# power.net
KiCad netlist of a schematic drawn in Altium Designer
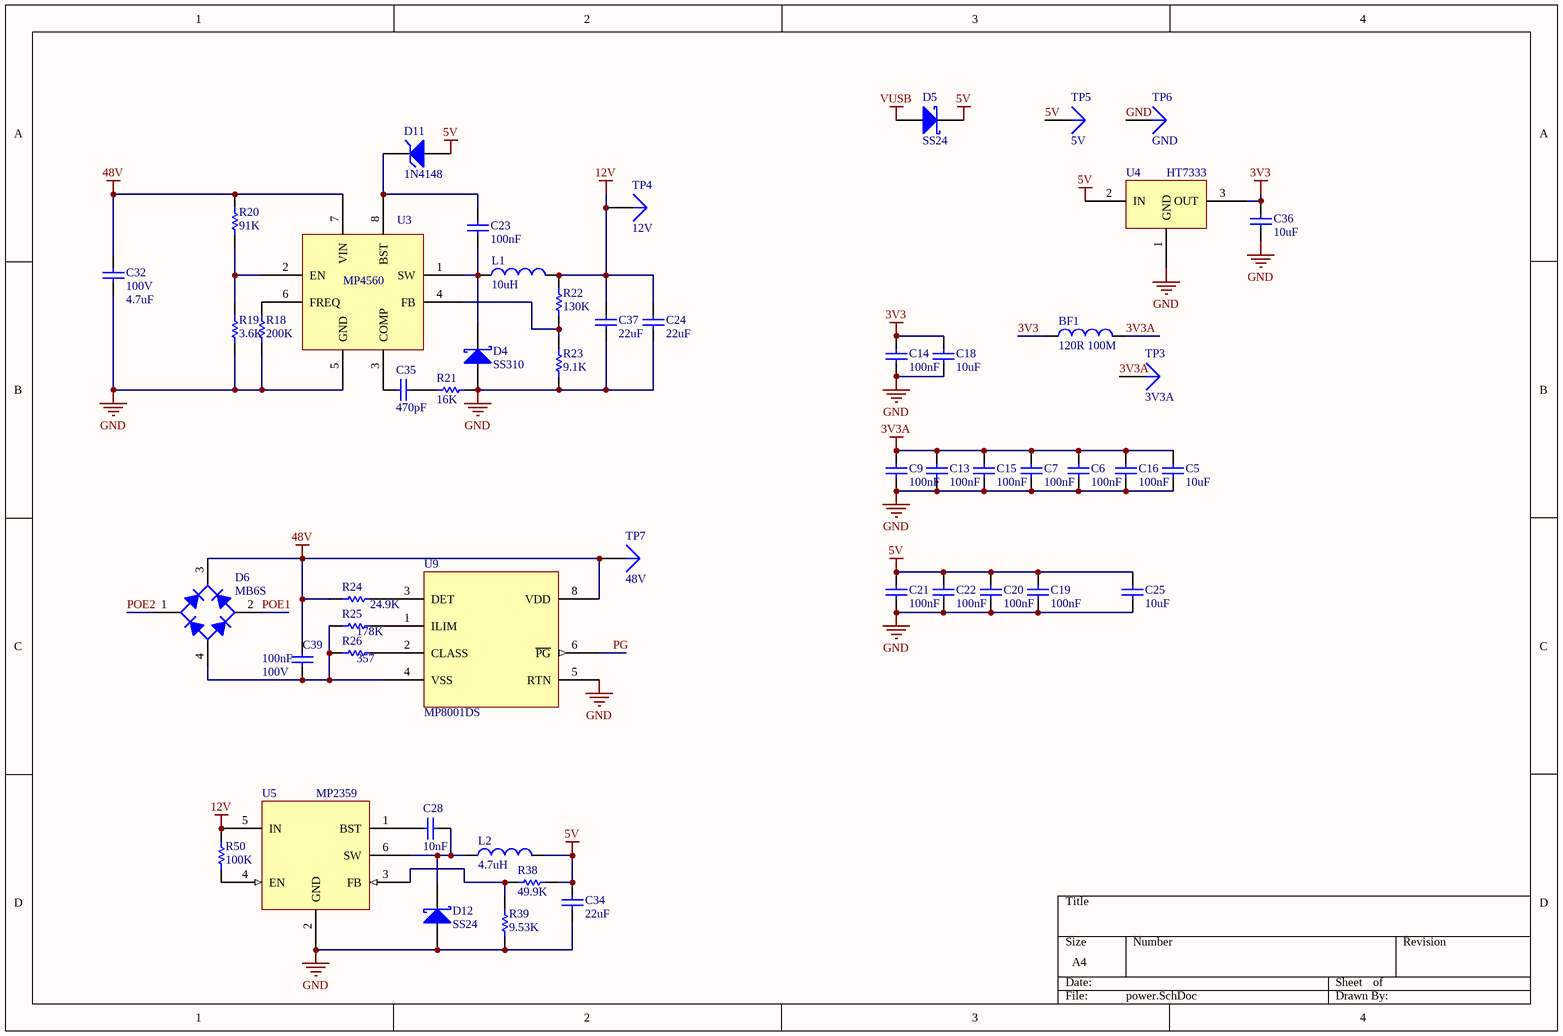
[diagram p0: power.SchDoc]

(export (version "E")
  (design (tool "Eeschema 10.0.6"))
  (components
    (comp (ref "BF1")
      (value "120R 100M")
      (footprint "L-1608[0603]")
      (fields (field (name "Comment") "GZ1608D121TF") (field (name "PUBLISHER") "Altium Limited"))
      (libsource (lib "Miscellaneous Devices") (part "Inductor"))
    )
    (comp (ref "C5")
      (value "10uF")
      (footprint "C-1608[0603]")
      (description "Capacitor (Semiconductor SIM Model)")
      (fields (field (name "Comment") "Cap Semi") (field (name "PUBLISHER") "Altium Limited"))
      (libsource (lib "Miscellaneous Devices") (part "Cap Semi"))
    )
    (comp (ref "C6")
      (value "100nF")
      (footprint "C-1608[0603]")
      (description "Capacitor (Semiconductor SIM Model)")
      (fields (field (name "Comment") "Cap Semi") (field (name "PUBLISHER") "Altium Limited"))
      (libsource (lib "Miscellaneous Devices") (part "Cap Semi"))
    )
    (comp (ref "C7")
      (value "100nF")
      (footprint "C-1608[0603]")
      (description "Capacitor (Semiconductor SIM Model)")
      (fields (field (name "Comment") "Cap Semi") (field (name "PUBLISHER") "Altium Limited"))
      (libsource (lib "Miscellaneous Devices") (part "Cap Semi"))
    )
    (comp (ref "C9")
      (value "100nF")
      (footprint "C-1608[0603]")
      (description "Capacitor (Semiconductor SIM Model)")
      (fields (field (name "Comment") "Cap Semi") (field (name "PUBLISHER") "Altium Limited"))
      (libsource (lib "Miscellaneous Devices") (part "Cap Semi"))
    )
    (comp (ref "C13")
      (value "100nF")
      (footprint "C-1608[0603]")
      (description "Capacitor (Semiconductor SIM Model)")
      (fields (field (name "Comment") "Cap Semi") (field (name "PUBLISHER") "Altium Limited"))
      (libsource (lib "Miscellaneous Devices") (part "Cap Semi"))
    )
    (comp (ref "C14")
      (value "100nF")
      (footprint "C-1608[0603]")
      (description "Capacitor (Semiconductor SIM Model)")
      (fields (field (name "Comment") "Cap Semi") (field (name "PUBLISHER") "Altium Limited"))
      (libsource (lib "Miscellaneous Devices") (part "Cap Semi"))
    )
    (comp (ref "C15")
      (value "100nF")
      (footprint "C-1608[0603]")
      (description "Capacitor (Semiconductor SIM Model)")
      (fields (field (name "Comment") "Cap Semi") (field (name "PUBLISHER") "Altium Limited"))
      (libsource (lib "Miscellaneous Devices") (part "Cap Semi"))
    )
    (comp (ref "C16")
      (value "100nF")
      (footprint "C-1608[0603]")
      (description "Capacitor (Semiconductor SIM Model)")
      (fields (field (name "Comment") "Cap Semi") (field (name "PUBLISHER") "Altium Limited"))
      (libsource (lib "Miscellaneous Devices") (part "Cap Semi"))
    )
    (comp (ref "C18")
      (value "10uF")
      (footprint "C-1608[0603]")
      (description "Capacitor (Semiconductor SIM Model)")
      (fields (field (name "Comment") "Cap Semi") (field (name "PUBLISHER") "Altium Limited"))
      (libsource (lib "Miscellaneous Devices") (part "Cap Semi"))
    )
    (comp (ref "C19")
      (value "100nF")
      (footprint "C-1608[0603]")
      (description "Capacitor (Semiconductor SIM Model)")
      (fields (field (name "Comment") "Cap Semi") (field (name "PUBLISHER") "Altium Limited"))
      (libsource (lib "Miscellaneous Devices") (part "Cap Semi"))
    )
    (comp (ref "C20")
      (value "100nF")
      (footprint "C-1608[0603]")
      (description "Capacitor (Semiconductor SIM Model)")
      (fields (field (name "Comment") "Cap Semi") (field (name "PUBLISHER") "Altium Limited"))
      (libsource (lib "Miscellaneous Devices") (part "Cap Semi"))
    )
    (comp (ref "C21")
      (value "100nF")
      (footprint "C-1608[0603]")
      (description "Capacitor (Semiconductor SIM Model)")
      (fields (field (name "Comment") "Cap Semi") (field (name "PUBLISHER") "Altium Limited"))
      (libsource (lib "Miscellaneous Devices") (part "Cap Semi"))
    )
    (comp (ref "C22")
      (value "100nF")
      (footprint "C-1608[0603]")
      (description "Capacitor (Semiconductor SIM Model)")
      (fields (field (name "Comment") "Cap Semi") (field (name "PUBLISHER") "Altium Limited"))
      (libsource (lib "Miscellaneous Devices") (part "Cap Semi"))
    )
    (comp (ref "C23")
      (value "100nF")
      (footprint "C-1608[0603]")
      (description "Capacitor (Semiconductor SIM Model)")
      (fields (field (name "Comment") "Cap Semi") (field (name "PUBLISHER") "Altium Limited"))
      (libsource (lib "Miscellaneous Devices") (part "Cap Semi"))
    )
    (comp (ref "C24")
      (value "22uF")
      (footprint "CAPC3225L")
      (description "Capacitor (Semiconductor SIM Model)")
      (fields (field (name "Comment") "Cap Semi") (field (name "PUBLISHER") "Altium Limited"))
      (libsource (lib "Miscellaneous Devices") (part "Cap Semi"))
    )
    (comp (ref "C25")
      (value "10uF")
      (footprint "C-1608[0603]")
      (description "Capacitor (Semiconductor SIM Model)")
      (fields (field (name "Comment") "Cap Semi") (field (name "PUBLISHER") "Altium Limited"))
      (libsource (lib "Miscellaneous Devices") (part "Cap Semi"))
    )
    (comp (ref "C28")
      (value "10nF")
      (footprint "C-1608[0603]")
      (description "Capacitor (Semiconductor SIM Model)")
      (fields (field (name "Comment") "Cap Semi") (field (name "PUBLISHER") "Altium Limited"))
      (libsource (lib "Miscellaneous Devices") (part "Cap Semi"))
    )
    (comp (ref "C32")
      (value "100V")
      (footprint "CAPC3216L")
      (description "Capacitor (Semiconductor SIM Model)")
      (fields (field (name "ALTIUM_VALUE") "4.7uF") (field (name "PUBLISHER") "Altium Limited"))
      (libsource (lib "Miscellaneous Devices") (part "Cap Semi"))
    )
    (comp (ref "C34")
      (value "22uF")
      (footprint "CAPC2512L")
      (description "Capacitor (Semiconductor SIM Model)")
      (fields (field (name "Comment") "Tantalum") (field (name "PUBLISHER") "Altium Limited"))
      (libsource (lib "Miscellaneous Devices") (part "Cap Semi"))
    )
    (comp (ref "C35")
      (value "470pF")
      (footprint "C-1608[0603]")
      (description "Capacitor (Semiconductor SIM Model)")
      (fields (field (name "Comment") "Cap Semi") (field (name "PUBLISHER") "Altium Limited"))
      (libsource (lib "Miscellaneous Devices") (part "Cap Semi"))
    )
    (comp (ref "C36")
      (value "10uF")
      (footprint "CAPC2512L")
      (description "Capacitor (Semiconductor SIM Model)")
      (fields (field (name "Comment") "Tantalum") (field (name "PUBLISHER") "Altium Limited"))
      (libsource (lib "Miscellaneous Devices") (part "Cap Semi"))
    )
    (comp (ref "C37")
      (value "22uF")
      (footprint "CAPC3225L")
      (description "Capacitor (Semiconductor SIM Model)")
      (fields (field (name "Comment") "Cap Semi") (field (name "PUBLISHER") "Altium Limited"))
      (libsource (lib "Miscellaneous Devices") (part "Cap Semi"))
    )
    (comp (ref "C39")
      (value "100V")
      (footprint "C-2012[0805]")
      (description "Capacitor (Semiconductor SIM Model)")
      (fields (field (name "ALTIUM_VALUE") "100nF") (field (name "PUBLISHER") "Altium Limited"))
      (libsource (lib "Miscellaneous Devices") (part "Cap Semi"))
    )
    (comp (ref "D4")
      (value "SS310")
      (footprint "DO-214AC")
      (description "Schottky Diode")
      (fields (field (name "PUBLISHER") "Altium Limited"))
      (libsource (lib "Miscellaneous Devices") (part "D Schottky"))
    )
    (comp (ref "D5")
      (value "SS24")
      (footprint "DO-214AC")
      (description "Schottky Diode")
      (fields (field (name "PUBLISHER") "Altium Limited"))
      (libsource (lib "Miscellaneous Devices") (part "D Schottky"))
    )
    (comp (ref "D6")
      (value "MB6S")
      (footprint "MB6S")
      (description "Full Wave Diode Bridge")
      (fields (field (name "PUBLISHER") "Altium Limited"))
      (libsource (lib "Miscellaneous Devices") (part "Bridge1"))
    )
    (comp (ref "D11")
      (value "1N4148")
      (footprint "LL-34")
      (description "Zener Diode")
      (fields (field (name "PUBLISHER") "Altium Limited"))
      (libsource (lib "Miscellaneous Devices") (part "D Zener"))
    )
    (comp (ref "D12")
      (value "SS24")
      (footprint "DO-214AC")
      (description "Schottky Diode")
      (fields (field (name "PUBLISHER") "Altium Limited"))
      (libsource (lib "Miscellaneous Devices") (part "D Schottky"))
    )
    (comp (ref "L1")
      (value "10uH")
      (footprint "L-5040")
      (description "Inductor")
      (fields (field (name "PUBLISHER") "Altium Limited"))
      (libsource (lib "Miscellaneous Devices") (part "Inductor"))
    )
    (comp (ref "L2")
      (value "4.7uH")
      (footprint "INDC4532N")
      (description "Inductor")
      (fields (field (name "PUBLISHER") "Altium Limited"))
      (libsource (lib "Miscellaneous Devices") (part "Inductor"))
    )
    (comp (ref "R18")
      (value "200K")
      (footprint "R-1608[0603]")
      (description "Semiconductor Resistor")
      (fields (field (name "Comment") "Res Semi") (field (name "PUBLISHER") "Altium Limited"))
      (libsource (lib "Miscellaneous Devices") (part "Res Semi"))
    )
    (comp (ref "R19")
      (value "3.6K")
      (footprint "R-1608[0603]")
      (description "Semiconductor Resistor")
      (fields (field (name "Comment") "Res Semi") (field (name "PUBLISHER") "Altium Limited"))
      (libsource (lib "Miscellaneous Devices") (part "Res Semi"))
    )
    (comp (ref "R20")
      (value "91K")
      (footprint "R-1608[0603]")
      (description "Semiconductor Resistor")
      (fields (field (name "Comment") "Res Semi") (field (name "PUBLISHER") "Altium Limited"))
      (libsource (lib "Miscellaneous Devices") (part "Res Semi"))
    )
    (comp (ref "R21")
      (value "16K")
      (footprint "R-1608[0603]")
      (description "Semiconductor Resistor")
      (fields (field (name "Comment") "Res Semi") (field (name "PUBLISHER") "Altium Limited"))
      (libsource (lib "Miscellaneous Devices") (part "Res Semi"))
    )
    (comp (ref "R22")
      (value "130K")
      (footprint "R-1608[0603]")
      (description "Semiconductor Resistor")
      (fields (field (name "Comment") "Res Semi") (field (name "PUBLISHER") "Altium Limited"))
      (libsource (lib "Miscellaneous Devices") (part "Res Semi"))
    )
    (comp (ref "R23")
      (value "9.1K")
      (footprint "R-1608[0603]")
      (description "Semiconductor Resistor")
      (fields (field (name "Comment") "Res Semi") (field (name "PUBLISHER") "Altium Limited"))
      (libsource (lib "Miscellaneous Devices") (part "Res Semi"))
    )
    (comp (ref "R24")
      (value "24.9K")
      (footprint "R-2012[0805]")
      (description "Semiconductor Resistor")
      (fields (field (name "Comment") "1/4W") (field (name "PUBLISHER") "Altium Limited"))
      (libsource (lib "Miscellaneous Devices") (part "Res Semi"))
    )
    (comp (ref "R25")
      (value "178K")
      (footprint "R-1608[0603]")
      (description "Semiconductor Resistor")
      (fields (field (name "Comment") "Res Semi") (field (name "PUBLISHER") "Altium Limited"))
      (libsource (lib "Miscellaneous Devices") (part "Res Semi"))
    )
    (comp (ref "R26")
      (value "357")
      (footprint "R-1608[0603]")
      (description "Semiconductor Resistor")
      (fields (field (name "Comment") "Res Semi") (field (name "PUBLISHER") "Altium Limited"))
      (libsource (lib "Miscellaneous Devices") (part "Res Semi"))
    )
    (comp (ref "R38")
      (value "49.9K")
      (footprint "R-1608[0603]")
      (description "Semiconductor Resistor")
      (fields (field (name "Comment") "Res Semi") (field (name "PUBLISHER") "Altium Limited"))
      (libsource (lib "Miscellaneous Devices") (part "Res Semi"))
    )
    (comp (ref "R39")
      (value "9.53K")
      (footprint "R-1608[0603]")
      (description "Semiconductor Resistor")
      (fields (field (name "Comment") "Res Semi") (field (name "PUBLISHER") "Altium Limited"))
      (libsource (lib "Miscellaneous Devices") (part "Res Semi"))
    )
    (comp (ref "R50")
      (value "100K")
      (footprint "R-1608[0603]")
      (description "Semiconductor Resistor")
      (fields (field (name "Comment") "Res Semi") (field (name "PUBLISHER") "Altium Limited"))
      (libsource (lib "Miscellaneous Devices") (part "Res Semi"))
    )
    (comp (ref "TP3")
      (value "3V3A")
      (footprint "TESTPOINT")
      (description "Plug")
      (fields (field (name "PUBLISHER") "Altium Limited"))
      (libsource (lib "Miscellaneous Connectors") (part "Plug"))
    )
    (comp (ref "TP4")
      (value "12V")
      (footprint "TESTPOINT")
      (description "Plug")
      (fields (field (name "PUBLISHER") "Altium Limited"))
      (libsource (lib "Miscellaneous Connectors") (part "Plug"))
    )
    (comp (ref "TP5")
      (value "5V")
      (footprint "TESTPOINT")
      (description "Plug")
      (fields (field (name "PUBLISHER") "Altium Limited"))
      (libsource (lib "Miscellaneous Connectors") (part "Plug"))
    )
    (comp (ref "TP6")
      (value "GND")
      (footprint "TESTPOINT")
      (description "Plug")
      (fields (field (name "PUBLISHER") "Altium Limited"))
      (libsource (lib "Miscellaneous Connectors") (part "Plug"))
    )
    (comp (ref "TP7")
      (value "48V")
      (footprint "TESTPOINT")
      (description "Plug")
      (fields (field (name "PUBLISHER") "Altium Limited"))
      (libsource (lib "Miscellaneous Connectors") (part "Plug"))
    )
    (comp (ref "U3")
      (value "MP4560")
      (footprint "MP1584")
      (description "2A, 2MHz, 55V Step-Down Converter")
      (libsource (lib "Schlib1") (part "MP4560"))
    )
    (comp (ref "U4")
      (value "HT7333")
      (footprint "SOT89")
      (description "Low Power Consumption LDO")
      (libsource (lib "Schlib1") (part "HT73XX"))
    )
    (comp (ref "U5")
      (value "MP2359")
      (footprint "SOT23-6")
      (description "1.2A, 24V, 1.4MHz  Step-Down Converter")
      (libsource (lib "Schlib1") (part "MP2359"))
    )
    (comp (ref "U9") (value "MP8001DS") (footprint "SOIC_E150_8") (libsource (lib "Schlib1") (part "MP8001")))
  )
  (nets
    (net (code "1") (name "/PG") (class "Default")
      (node (ref "U9") (pin "6") (pinfunction "~{PG}_6") (pintype "output"))
    )
    (net (code "2") (name "/POE1") (class "Default")
      (node (ref "D6") (pin "2") (pinfunction "C_2") (pintype "passive"))
    )
    (net (code "3") (name "/POE2") (class "Default")
      (node (ref "D6") (pin "1") (pinfunction "C_1") (pintype "passive"))
    )
    (net (code "4") (name "3V3") (class "Default")
      (node (ref "BF1") (pin "1") (pinfunction "1_1") (pintype "passive"))
      (node (ref "C14") (pin "2") (pinfunction "2_2") (pintype "passive"))
      (node (ref "C18") (pin "2") (pinfunction "2_2") (pintype "passive"))
      (node (ref "C36") (pin "1") (pinfunction "1_1") (pintype "passive"))
      (node (ref "U4") (pin "3") (pinfunction "OUT_3") (pintype "passive"))
    )
    (net (code "5") (name "3V3A") (class "Default")
      (node (ref "BF1") (pin "2") (pinfunction "2_2") (pintype "passive"))
      (node (ref "C13") (pin "2") (pinfunction "2_2") (pintype "passive"))
      (node (ref "C15") (pin "2") (pinfunction "2_2") (pintype "passive"))
      (node (ref "C16") (pin "2") (pinfunction "2_2") (pintype "passive"))
      (node (ref "C5") (pin "2") (pinfunction "2_2") (pintype "passive"))
      (node (ref "C6") (pin "2") (pinfunction "2_2") (pintype "passive"))
      (node (ref "C7") (pin "2") (pinfunction "2_2") (pintype "passive"))
      (node (ref "C9") (pin "2") (pinfunction "2_2") (pintype "passive"))
      (node (ref "TP3") (pin "1") (pinfunction "1_1") (pintype "passive"))
    )
    (net (code "6") (name "5V") (class "Default")
      (node (ref "C19") (pin "2") (pinfunction "2_2") (pintype "passive"))
      (node (ref "C20") (pin "2") (pinfunction "2_2") (pintype "passive"))
      (node (ref "C21") (pin "2") (pinfunction "2_2") (pintype "passive"))
      (node (ref "C22") (pin "2") (pinfunction "2_2") (pintype "passive"))
      (node (ref "C25") (pin "2") (pinfunction "2_2") (pintype "passive"))
      (node (ref "C34") (pin "1") (pinfunction "1_1") (pintype "passive"))
      (node (ref "D11") (pin "1") (pinfunction "A_1") (pintype "passive"))
      (node (ref "D5") (pin "2") (pinfunction "K_2") (pintype "passive"))
      (node (ref "L2") (pin "2") (pinfunction "2_2") (pintype "passive"))
      (node (ref "R38") (pin "1") (pinfunction "1_1") (pintype "passive"))
      (node (ref "TP5") (pin "1") (pinfunction "1_1") (pintype "passive"))
      (node (ref "U4") (pin "2") (pinfunction "IN_2") (pintype "passive"))
    )
    (net (code "7") (name "12V") (class "Default")
      (node (ref "C24") (pin "1") (pinfunction "1_1") (pintype "passive"))
      (node (ref "C37") (pin "1") (pinfunction "1_1") (pintype "passive"))
      (node (ref "L1") (pin "2") (pinfunction "2_2") (pintype "passive"))
      (node (ref "R22") (pin "2") (pinfunction "2_2") (pintype "passive"))
      (node (ref "R50") (pin "1") (pinfunction "1_1") (pintype "passive"))
      (node (ref "TP4") (pin "1") (pinfunction "1_1") (pintype "passive"))
      (node (ref "U5") (pin "5") (pinfunction "IN_5") (pintype "power_in"))
    )
    (net (code "8") (name "48V") (class "Default")
      (node (ref "C32") (pin "2") (pinfunction "2_2") (pintype "passive"))
      (node (ref "C39") (pin "2") (pinfunction "2_2") (pintype "passive"))
      (node (ref "D6") (pin "3") (pinfunction "K_3") (pintype "passive"))
      (node (ref "R20") (pin "2") (pinfunction "2_2") (pintype "passive"))
      (node (ref "R24") (pin "2") (pinfunction "2_2") (pintype "passive"))
      (node (ref "TP7") (pin "1") (pinfunction "1_1") (pintype "passive"))
      (node (ref "U3") (pin "7") (pinfunction "VIN_7") (pintype "passive"))
      (node (ref "U9") (pin "8") (pinfunction "VDD_8") (pintype "power_in"))
    )
    (net (code "9") (name "GND") (class "Default")
      (node (ref "C13") (pin "1") (pinfunction "1_1") (pintype "passive"))
      (node (ref "C14") (pin "1") (pinfunction "1_1") (pintype "passive"))
      (node (ref "C15") (pin "1") (pinfunction "1_1") (pintype "passive"))
      (node (ref "C16") (pin "1") (pinfunction "1_1") (pintype "passive"))
      (node (ref "C18") (pin "1") (pinfunction "1_1") (pintype "passive"))
      (node (ref "C19") (pin "1") (pinfunction "1_1") (pintype "passive"))
      (node (ref "C20") (pin "1") (pinfunction "1_1") (pintype "passive"))
      (node (ref "C21") (pin "1") (pinfunction "1_1") (pintype "passive"))
      (node (ref "C22") (pin "1") (pinfunction "1_1") (pintype "passive"))
      (node (ref "C24") (pin "2") (pinfunction "2_2") (pintype "passive"))
      (node (ref "C25") (pin "1") (pinfunction "1_1") (pintype "passive"))
      (node (ref "C32") (pin "1") (pinfunction "1_1") (pintype "passive"))
      (node (ref "C34") (pin "2") (pinfunction "2_2") (pintype "passive"))
      (node (ref "C36") (pin "2") (pinfunction "2_2") (pintype "passive"))
      (node (ref "C37") (pin "2") (pinfunction "2_2") (pintype "passive"))
      (node (ref "C5") (pin "1") (pinfunction "1_1") (pintype "passive"))
      (node (ref "C6") (pin "1") (pinfunction "1_1") (pintype "passive"))
      (node (ref "C7") (pin "1") (pinfunction "1_1") (pintype "passive"))
      (node (ref "C9") (pin "1") (pinfunction "1_1") (pintype "passive"))
      (node (ref "D12") (pin "1") (pinfunction "A_1") (pintype "passive"))
      (node (ref "D4") (pin "1") (pinfunction "A_1") (pintype "passive"))
      (node (ref "R18") (pin "1") (pinfunction "1_1") (pintype "passive"))
      (node (ref "R19") (pin "1") (pinfunction "1_1") (pintype "passive"))
      (node (ref "R21") (pin "1") (pinfunction "1_1") (pintype "passive"))
      (node (ref "R23") (pin "1") (pinfunction "1_1") (pintype "passive"))
      (node (ref "R39") (pin "1") (pinfunction "1_1") (pintype "passive"))
      (node (ref "TP6") (pin "1") (pinfunction "1_1") (pintype "passive"))
      (node (ref "U3") (pin "5") (pinfunction "GND_5") (pintype "passive"))
      (node (ref "U4") (pin "1") (pinfunction "GND_1") (pintype "passive"))
      (node (ref "U5") (pin "2") (pinfunction "GND_2") (pintype "passive"))
      (node (ref "U9") (pin "5") (pinfunction "RTN_5") (pintype "passive"))
    )
    (net (code "10") (name "Net-(C35-Pad2)") (class "Default")
      (node (ref "C35") (pin "2") (pinfunction "2_2") (pintype "passive"))
      (node (ref "R21") (pin "2") (pinfunction "2_2") (pintype "passive"))
    )
    (net (code "11") (name "Net-(D4-K)") (class "Default")
      (node (ref "C23") (pin "1") (pinfunction "1_1") (pintype "passive"))
      (node (ref "D4") (pin "2") (pinfunction "K_2") (pintype "passive"))
      (node (ref "L1") (pin "1") (pinfunction "1_1") (pintype "passive"))
      (node (ref "U3") (pin "1") (pinfunction "SW_1") (pintype "passive"))
    )
    (net (code "12") (name "Net-(D6-A)") (class "Default")
      (node (ref "C39") (pin "1") (pinfunction "1_1") (pintype "passive"))
      (node (ref "D6") (pin "4") (pinfunction "A_4") (pintype "passive"))
      (node (ref "R25") (pin "2") (pinfunction "2_2") (pintype "passive"))
      (node (ref "R26") (pin "2") (pinfunction "2_2") (pintype "passive"))
      (node (ref "U9") (pin "4") (pinfunction "VSS_4") (pintype "passive"))
    )
    (net (code "13") (name "Net-(D11-K)") (class "Default")
      (node (ref "C23") (pin "2") (pinfunction "2_2") (pintype "passive"))
      (node (ref "D11") (pin "2") (pinfunction "K_2") (pintype "passive"))
      (node (ref "U3") (pin "8") (pinfunction "BST_8") (pintype "passive"))
    )
    (net (code "14") (name "Net-(D12-K)") (class "Default")
      (node (ref "C28") (pin "2") (pinfunction "2_2") (pintype "passive"))
      (node (ref "D12") (pin "2") (pinfunction "K_2") (pintype "passive"))
      (node (ref "L2") (pin "1") (pinfunction "1_1") (pintype "passive"))
      (node (ref "U5") (pin "6") (pinfunction "SW_6") (pintype "power_in"))
    )
    (net (code "15") (name "Net-(U3-COMP)") (class "Default")
      (node (ref "C35") (pin "1") (pinfunction "1_1") (pintype "passive"))
      (node (ref "U3") (pin "3") (pinfunction "COMP_3") (pintype "passive"))
    )
    (net (code "16") (name "Net-(U3-EN)") (class "Default")
      (node (ref "R19") (pin "2") (pinfunction "2_2") (pintype "passive"))
      (node (ref "R20") (pin "1") (pinfunction "1_1") (pintype "passive"))
      (node (ref "U3") (pin "2") (pinfunction "EN_2") (pintype "passive"))
    )
    (net (code "17") (name "Net-(U3-FB)") (class "Default")
      (node (ref "R22") (pin "1") (pinfunction "1_1") (pintype "passive"))
      (node (ref "R23") (pin "2") (pinfunction "2_2") (pintype "passive"))
      (node (ref "U3") (pin "4") (pinfunction "FB_4") (pintype "passive"))
    )
    (net (code "18") (name "Net-(U3-FREQ)") (class "Default")
      (node (ref "R18") (pin "2") (pinfunction "2_2") (pintype "passive"))
      (node (ref "U3") (pin "6") (pinfunction "FREQ_6") (pintype "passive"))
    )
    (net (code "19") (name "Net-(U5-BST)") (class "Default")
      (node (ref "C28") (pin "1") (pinfunction "1_1") (pintype "passive"))
      (node (ref "U5") (pin "1") (pinfunction "BST_1") (pintype "passive"))
    )
    (net (code "20") (name "Net-(U5-EN)") (class "Default")
      (node (ref "R50") (pin "2") (pinfunction "2_2") (pintype "passive"))
      (node (ref "U5") (pin "4") (pinfunction "EN_4") (pintype "input"))
    )
    (net (code "21") (name "Net-(U5-FB)") (class "Default")
      (node (ref "R38") (pin "2") (pinfunction "2_2") (pintype "passive"))
      (node (ref "R39") (pin "2") (pinfunction "2_2") (pintype "passive"))
      (node (ref "U5") (pin "3") (pinfunction "FB_3") (pintype "input"))
    )
    (net (code "22") (name "Net-(U9-CLASS)") (class "Default")
      (node (ref "R26") (pin "1") (pinfunction "1_1") (pintype "passive"))
      (node (ref "U9") (pin "2") (pinfunction "CLASS_2") (pintype "passive"))
    )
    (net (code "23") (name "Net-(U9-DET)") (class "Default")
      (node (ref "R24") (pin "1") (pinfunction "1_1") (pintype "passive"))
      (node (ref "U9") (pin "3") (pinfunction "DET_3") (pintype "passive"))
    )
    (net (code "24") (name "Net-(U9-ILIM)") (class "Default")
      (node (ref "R25") (pin "1") (pinfunction "1_1") (pintype "passive"))
      (node (ref "U9") (pin "1") (pinfunction "ILIM_1") (pintype "passive"))
    )
    (net (code "25") (name "VUSB") (class "Default")
      (node (ref "D5") (pin "1") (pinfunction "A_1") (pintype "passive"))
    )
  )
)
